# CA_kit_v02.net
KiCad netlist of a schematic drawn in EAGLE
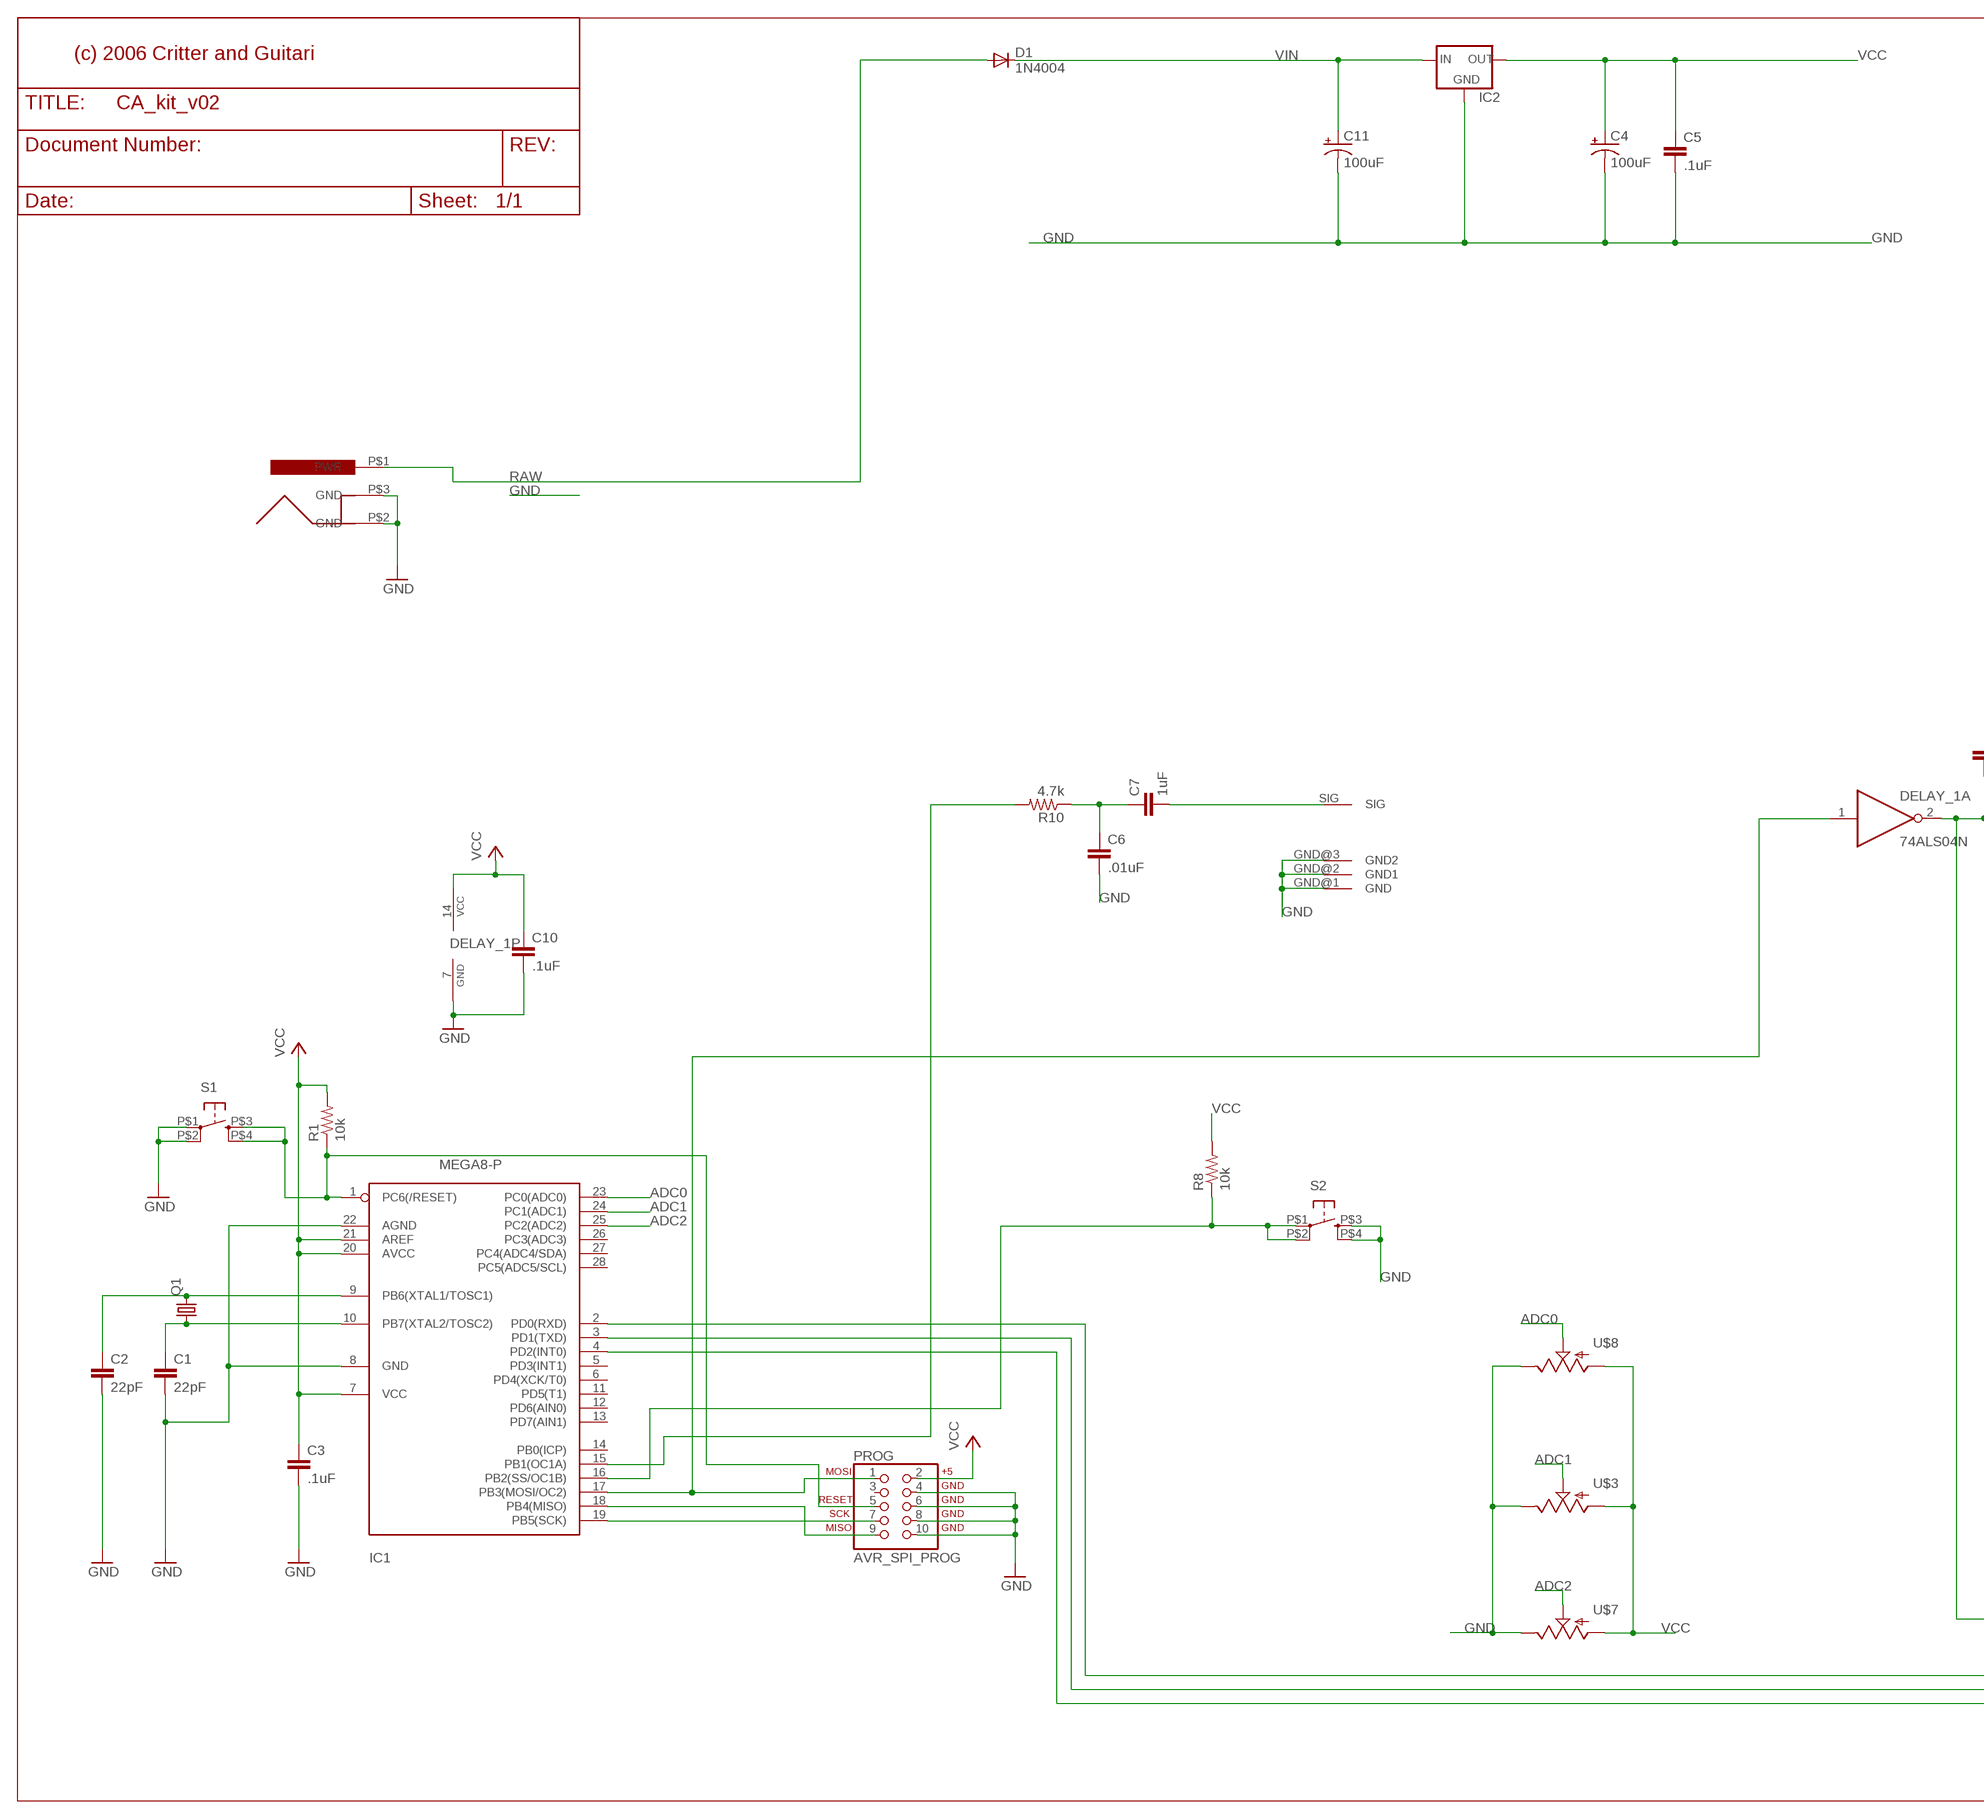
[diagram p0: schematic, sheet 1, part 1 of 2]
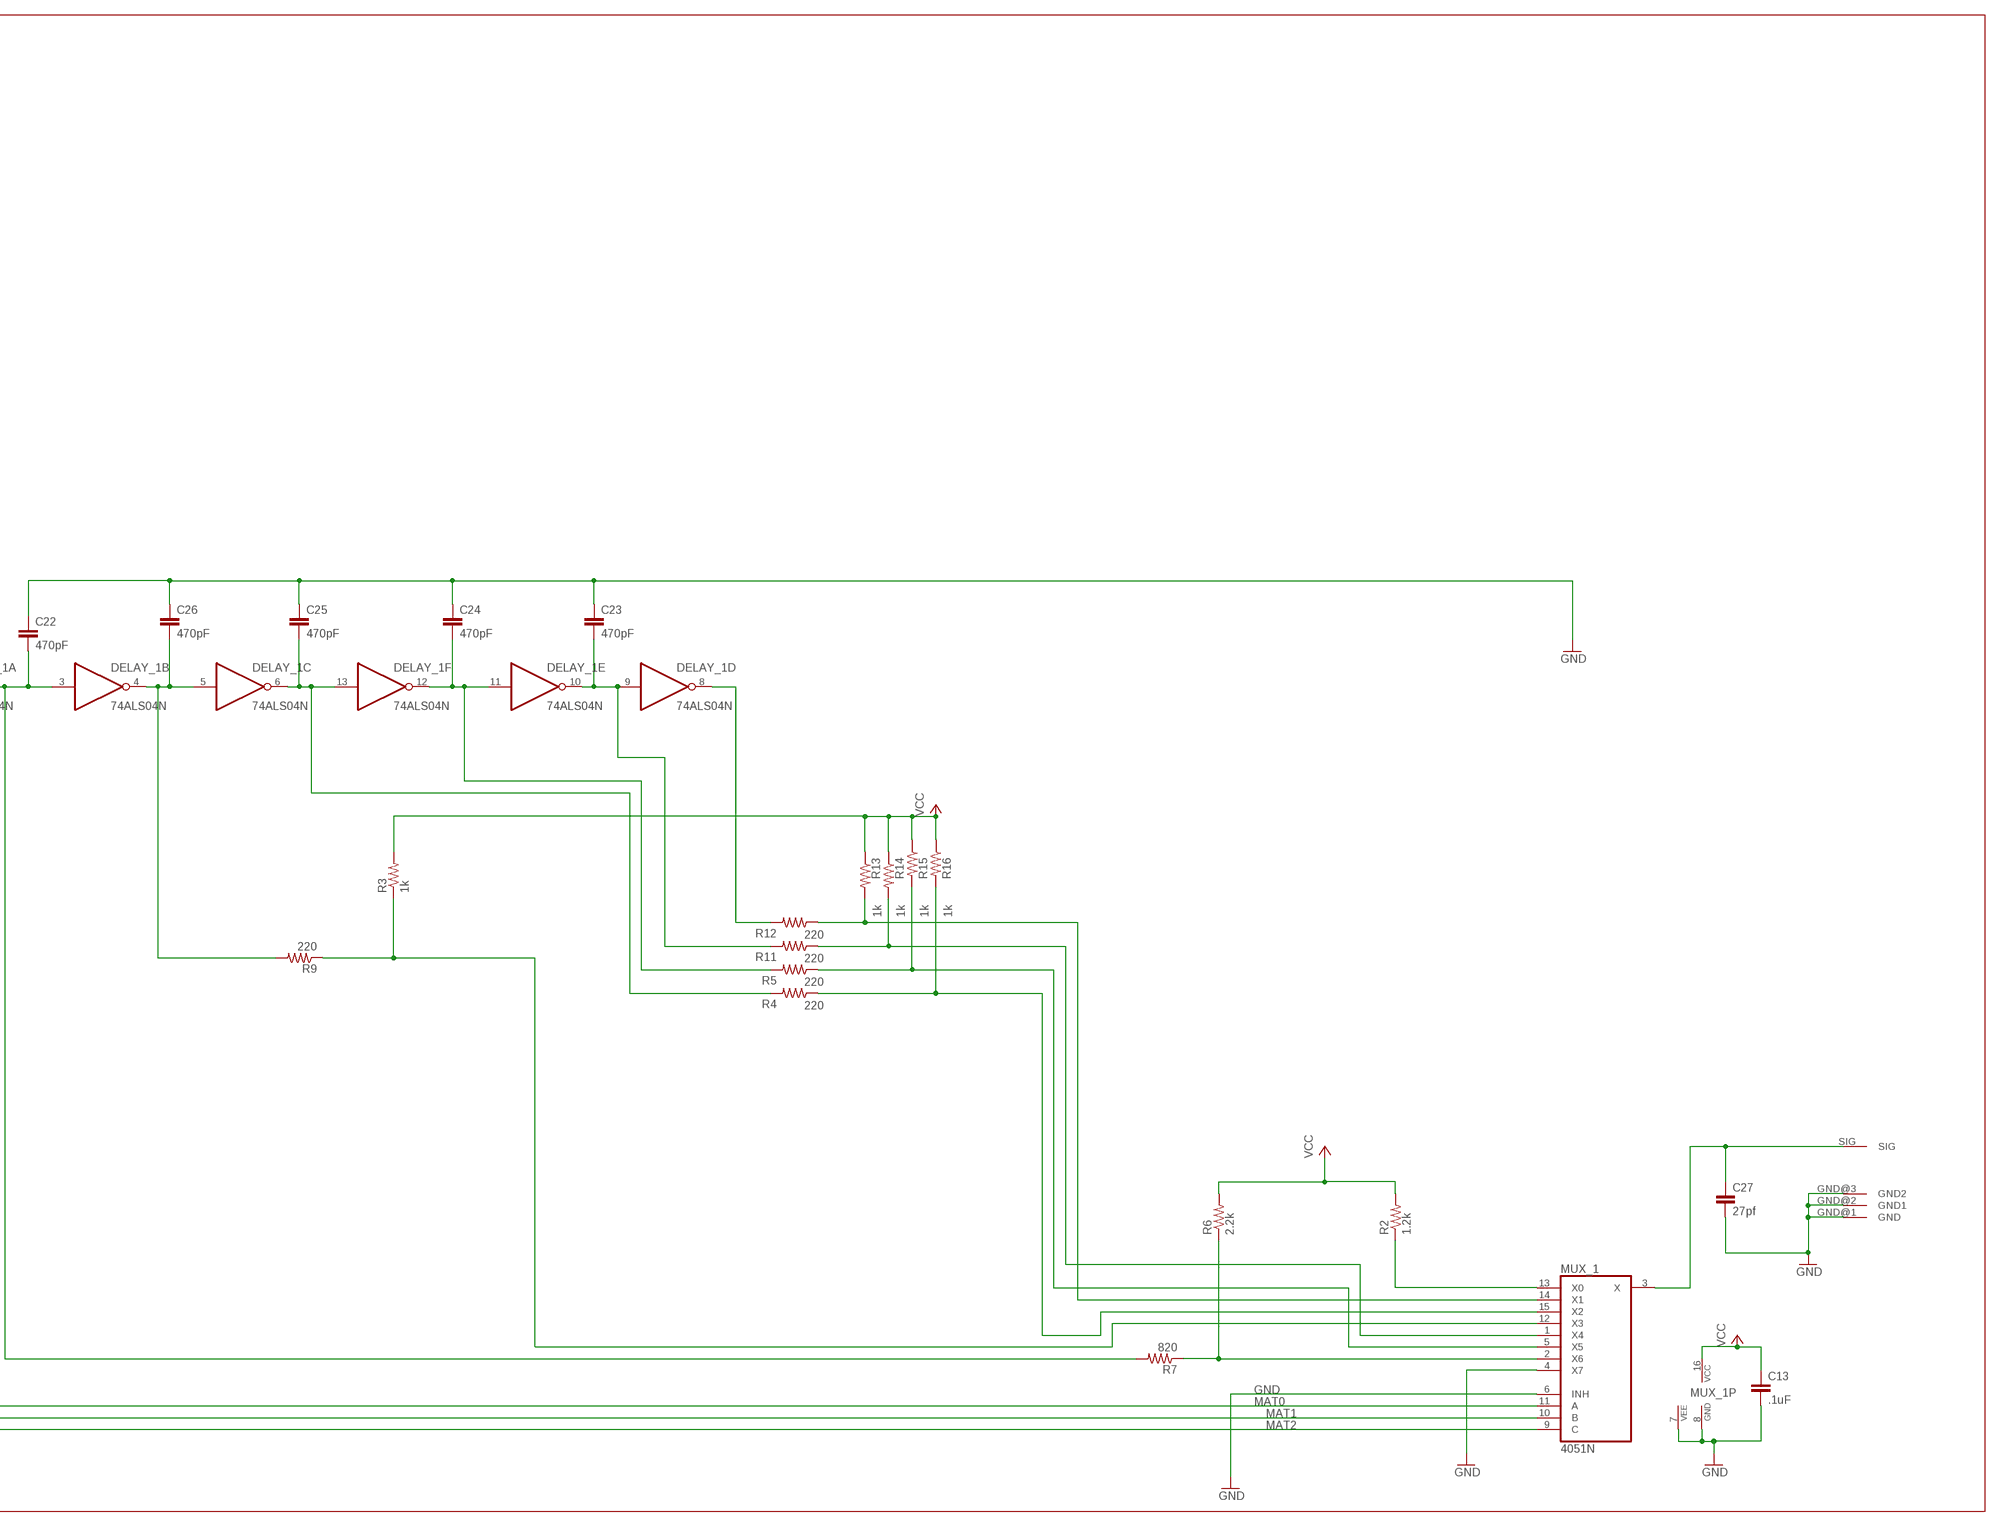
[diagram p1: schematic, sheet 1, part 2 of 2]

(export (version "E")
  (design (tool "Eeschema 10.0.6"))
  (components
    (comp (ref "C1")
      (value "22pF")
      (footprint "eagle-import:C025-025X050")
      (libsource (lib "eagle-import") (part "CAP025-025X050"))
    )
    (comp (ref "C2")
      (value "22pF")
      (footprint "eagle-import:C025-025X050")
      (libsource (lib "eagle-import") (part "CAP025-025X050"))
    )
    (comp (ref "C3")
      (value ".1uF")
      (footprint "eagle-import:C025-025X050")
      (libsource (lib "eagle-import") (part "CAP025-025X050"))
    )
    (comp (ref "C4")
      (value "100uF")
      (footprint "eagle-import:E3,5-8")
      (libsource (lib "eagle-import") (part "CPOL-USE3.5-8"))
    )
    (comp (ref "C5")
      (value ".1uF")
      (footprint "eagle-import:C025-025X050")
      (libsource (lib "eagle-import") (part "CAP025-025X050"))
    )
    (comp (ref "C6")
      (value ".01uF")
      (footprint "eagle-import:C025-025X050")
      (libsource (lib "eagle-import") (part "CAP025-025X050"))
    )
    (comp (ref "C7")
      (value "1uF")
      (footprint "eagle-import:C025-025X050")
      (libsource (lib "eagle-import") (part "CAP025-025X050"))
    )
    (comp (ref "C10")
      (value ".1uF")
      (footprint "eagle-import:C025-025X050")
      (libsource (lib "eagle-import") (part "CAP025-025X050"))
    )
    (comp (ref "C11")
      (value "100uF")
      (footprint "eagle-import:E3,5-8")
      (libsource (lib "eagle-import") (part "CPOL-USE3.5-8"))
    )
    (comp (ref "C13")
      (value ".1uF")
      (footprint "eagle-import:C025-025X050")
      (libsource (lib "eagle-import") (part "CAP025-025X050"))
    )
    (comp (ref "C22")
      (value "470pF")
      (footprint "eagle-import:C025-025X050")
      (libsource (lib "eagle-import") (part "CAP025-025X050"))
    )
    (comp (ref "C23")
      (value "470pF")
      (footprint "eagle-import:C025-025X050")
      (libsource (lib "eagle-import") (part "CAP025-025X050"))
    )
    (comp (ref "C24")
      (value "470pF")
      (footprint "eagle-import:C025-025X050")
      (libsource (lib "eagle-import") (part "CAP025-025X050"))
    )
    (comp (ref "C25")
      (value "470pF")
      (footprint "eagle-import:C025-025X050")
      (libsource (lib "eagle-import") (part "CAP025-025X050"))
    )
    (comp (ref "C26")
      (value "470pF")
      (footprint "eagle-import:C025-025X050")
      (libsource (lib "eagle-import") (part "CAP025-025X050"))
    )
    (comp (ref "C27")
      (value "27pf")
      (footprint "eagle-import:C025-025X050")
      (libsource (lib "eagle-import") (part "CAP025-025X050"))
    )
    (comp (ref "D1")
      (value "1N4004")
      (footprint "eagle-import:DO41-10")
      (libsource (lib "eagle-import") (part "1N4004"))
    )
    (comp (ref "DELAY_1")
      (value "74ALS04N")
      (footprint "eagle-import:DIL14")
      (libsource (lib "eagle-import") (part "7404NALS"))
    )
    (comp (ref "IC1")
      (value "MEGA8-P")
      (footprint "eagle-import:DIL28-3")
      (libsource (lib "eagle-import") (part "MEGA8-P"))
    )
    (comp (ref "IC2")
      (value "78XXS")
      (footprint "eagle-import:78XXS")
      (libsource (lib "eagle-import") (part "78XXS"))
    )
    (comp (ref "MUX_1")
      (value "4051N")
      (footprint "eagle-import:DIL16")
      (libsource (lib "eagle-import") (part "4051N"))
    )
    (comp (ref "PROG")
      (value "AVR_SPI_PROG")
      (footprint "eagle-import:PINHEAD_2X05")
      (libsource (lib "eagle-import") (part "AVR_SPI_PROG"))
    )
    (comp (ref "Q1")
      (value "CRYSTALHC49UV")
      (footprint "eagle-import:HC49U-V")
      (libsource (lib "eagle-import") (part "CRYSTALHC49UV"))
    )
    (comp (ref "R1")
      (value "10k")
      (footprint "eagle-import:0204V")
      (libsource (lib "eagle-import") (part "RES0204V"))
    )
    (comp (ref "R2")
      (value "1.2k")
      (footprint "eagle-import:0204V")
      (libsource (lib "eagle-import") (part "RES0204V"))
    )
    (comp (ref "R3")
      (value "1k")
      (footprint "eagle-import:0204V")
      (libsource (lib "eagle-import") (part "RES0204V"))
    )
    (comp (ref "R4")
      (value "220")
      (footprint "eagle-import:0204V")
      (libsource (lib "eagle-import") (part "RES0204V"))
    )
    (comp (ref "R5")
      (value "220")
      (footprint "eagle-import:0204V")
      (libsource (lib "eagle-import") (part "RES0204V"))
    )
    (comp (ref "R6")
      (value "2.2k")
      (footprint "eagle-import:0204V")
      (libsource (lib "eagle-import") (part "RES0204V"))
    )
    (comp (ref "R7")
      (value "820")
      (footprint "eagle-import:0204V")
      (libsource (lib "eagle-import") (part "RES0204V"))
    )
    (comp (ref "R8")
      (value "10k")
      (footprint "eagle-import:0204V")
      (libsource (lib "eagle-import") (part "RES0204V"))
    )
    (comp (ref "R9")
      (value "220")
      (footprint "eagle-import:0204V")
      (libsource (lib "eagle-import") (part "RES0204V"))
    )
    (comp (ref "R10")
      (value "4.7k")
      (footprint "eagle-import:0204V")
      (libsource (lib "eagle-import") (part "RES0204V"))
    )
    (comp (ref "R11")
      (value "220")
      (footprint "eagle-import:0204V")
      (libsource (lib "eagle-import") (part "RES0204V"))
    )
    (comp (ref "R12")
      (value "220")
      (footprint "eagle-import:0204V")
      (libsource (lib "eagle-import") (part "RES0204V"))
    )
    (comp (ref "R13")
      (value "1k")
      (footprint "eagle-import:0204V")
      (libsource (lib "eagle-import") (part "RES0204V"))
    )
    (comp (ref "R14")
      (value "1k")
      (footprint "eagle-import:0204V")
      (libsource (lib "eagle-import") (part "RES0204V"))
    )
    (comp (ref "R15")
      (value "1k")
      (footprint "eagle-import:0204V")
      (libsource (lib "eagle-import") (part "RES0204V"))
    )
    (comp (ref "R16")
      (value "1k")
      (footprint "eagle-import:0204V")
      (libsource (lib "eagle-import") (part "RES0204V"))
    )
    (comp (ref "S1")
      (value "TAC_SWITCHKSA_SEALED_TAC_SWITCH")
      (footprint "eagle-import:KSA_SEALED_TAC_SWITCH")
      (libsource (lib "eagle-import") (part "TAC_SWITCHKSA_SEALED_TAC_SWITCH"))
    )
    (comp (ref "S2")
      (value "TAC_SWITCHKSA_SEALED_TAC_SWITCH")
      (footprint "eagle-import:KSA_SEALED_TAC_SWITCH")
      (libsource (lib "eagle-import") (part "TAC_SWITCHKSA_SEALED_TAC_SWITCH"))
    )
    (comp (ref "U$1")
      (value "POWER_JACK")
      (footprint "eagle-import:POWER_JACK")
      (libsource (lib "eagle-import") (part "POWER_JACKTHRU-HOLE"))
    )
    (comp (ref "U$3")
      (value "POT")
      (footprint "eagle-import:ALPS_POT")
      (libsource (lib "eagle-import") (part "POT"))
    )
    (comp (ref "U$5")
      (value "PHONO_PLUG")
      (footprint "eagle-import:PHONO_PCB")
      (libsource (lib "eagle-import") (part "PHONO_PLUG"))
    )
    (comp (ref "U$6")
      (value "PHONO_PLUG")
      (footprint "eagle-import:PHONO_PCB")
      (libsource (lib "eagle-import") (part "PHONO_PLUG"))
    )
    (comp (ref "U$7")
      (value "POT")
      (footprint "eagle-import:ALPS_POT")
      (libsource (lib "eagle-import") (part "POT"))
    )
    (comp (ref "U$8")
      (value "POT")
      (footprint "eagle-import:ALPS_POT")
      (libsource (lib "eagle-import") (part "POT"))
    )
  )
  (nets
    (net (code "1") (name "/ADC0") (class "Default")
      (node (ref "IC1") (pin "23") (pinfunction "PC0(ADC0)_23") (pintype "bidirectional"))
      (node (ref "U$8") (pin "P$2") (pinfunction "S_P$2") (pintype "passive"))
    )
    (net (code "2") (name "/ADC1") (class "Default")
      (node (ref "IC1") (pin "24") (pinfunction "PC1(ADC1)_24") (pintype "bidirectional"))
      (node (ref "U$3") (pin "P$2") (pinfunction "S_P$2") (pintype "passive"))
    )
    (net (code "3") (name "/ADC2") (class "Default")
      (node (ref "IC1") (pin "25") (pinfunction "PC2(ADC2)_25") (pintype "bidirectional"))
      (node (ref "U$7") (pin "P$2") (pinfunction "S_P$2") (pintype "passive"))
    )
    (net (code "4") (name "/MAT0") (class "Default")
      (node (ref "IC1") (pin "2") (pinfunction "PD0(RXD)_2") (pintype "bidirectional"))
      (node (ref "MUX_1") (pin "11") (pinfunction "A_11") (pintype "input"))
    )
    (net (code "5") (name "/MAT1") (class "Default")
      (node (ref "IC1") (pin "3") (pinfunction "PD1(TXD)_3") (pintype "bidirectional"))
      (node (ref "MUX_1") (pin "10") (pinfunction "B_10") (pintype "input"))
    )
    (net (code "6") (name "/MAT2") (class "Default")
      (node (ref "IC1") (pin "4") (pinfunction "PD2(INT0)_4") (pintype "bidirectional"))
      (node (ref "MUX_1") (pin "9") (pinfunction "C_9") (pintype "input"))
    )
    (net (code "7") (name "/RAW") (class "Default")
      (node (ref "D1") (pin "A") (pinfunction "A_A") (pintype "passive"))
      (node (ref "U$1") (pin "P$1") (pinfunction "PWR_P$1") (pintype "bidirectional"))
    )
    (net (code "8") (name "/VIN") (class "Default")
      (node (ref "C11") (pin "+") (pinfunction "+_+") (pintype "passive"))
      (node (ref "D1") (pin "C") (pinfunction "C_C") (pintype "passive"))
      (node (ref "IC2") (pin "IN") (pinfunction "IN_IN") (pintype "input"))
    )
    (net (code "9") (name "GND") (class "Default")
      (node (ref "C1") (pin "2") (pinfunction "2_2") (pintype "passive"))
      (node (ref "C10") (pin "2") (pinfunction "2_2") (pintype "passive"))
      (node (ref "C11") (pin "-") (pinfunction "-_-") (pintype "passive"))
      (node (ref "C13") (pin "2") (pinfunction "2_2") (pintype "passive"))
      (node (ref "C2") (pin "2") (pinfunction "2_2") (pintype "passive"))
      (node (ref "C22") (pin "1") (pinfunction "1_1") (pintype "passive"))
      (node (ref "C23") (pin "1") (pinfunction "1_1") (pintype "passive"))
      (node (ref "C24") (pin "1") (pinfunction "1_1") (pintype "passive"))
      (node (ref "C25") (pin "1") (pinfunction "1_1") (pintype "passive"))
      (node (ref "C26") (pin "1") (pinfunction "1_1") (pintype "passive"))
      (node (ref "C27") (pin "2") (pinfunction "2_2") (pintype "passive"))
      (node (ref "C3") (pin "2") (pinfunction "2_2") (pintype "passive"))
      (node (ref "C4") (pin "-") (pinfunction "-_-") (pintype "passive"))
      (node (ref "C5") (pin "2") (pinfunction "2_2") (pintype "passive"))
      (node (ref "C6") (pin "2") (pinfunction "2_2") (pintype "passive"))
      (node (ref "DELAY_1") (pin "7") (pinfunction "GND_7") (pintype "power_in"))
      (node (ref "IC1") (pin "22") (pinfunction "AGND_22") (pintype "bidirectional"))
      (node (ref "IC1") (pin "8") (pinfunction "GND_8") (pintype "bidirectional"))
      (node (ref "IC2") (pin "GND") (pinfunction "GND_GND") (pintype "input"))
      (node (ref "MUX_1") (pin "4") (pinfunction "X7_4") (pintype "bidirectional"))
      (node (ref "MUX_1") (pin "6") (pinfunction "INH_6") (pintype "input"))
      (node (ref "MUX_1") (pin "7") (pinfunction "VEE_7") (pintype "power_in"))
      (node (ref "MUX_1") (pin "8") (pinfunction "GND_8") (pintype "power_in"))
      (node (ref "PROG") (pin "10") (pinfunction "10_10") (pintype "passive"))
      (node (ref "PROG") (pin "4") (pinfunction "4_4") (pintype "passive"))
      (node (ref "PROG") (pin "6") (pinfunction "6_6") (pintype "passive"))
      (node (ref "PROG") (pin "8") (pinfunction "8_8") (pintype "passive"))
      (node (ref "S1") (pin "P$1") (pinfunction "P_P$1") (pintype "passive"))
      (node (ref "S1") (pin "P$2") (pinfunction "P1_P$2") (pintype "passive"))
      (node (ref "S2") (pin "P$3") (pinfunction "S_P$3") (pintype "passive"))
      (node (ref "S2") (pin "P$4") (pinfunction "S1_P$4") (pintype "passive"))
      (node (ref "U$1") (pin "P$2") (pinfunction "GND_P$2") (pintype "bidirectional"))
      (node (ref "U$1") (pin "P$3") (pinfunction "GND_P$3") (pintype "bidirectional"))
      (node (ref "U$3") (pin "P$1") (pinfunction "E_P$1") (pintype "passive"))
      (node (ref "U$5") (pin "GND@1") (pinfunction "GND_GND@1") (pintype "bidirectional"))
      (node (ref "U$5") (pin "GND@2") (pinfunction "GND1_GND@2") (pintype "bidirectional"))
      (node (ref "U$5") (pin "GND@3") (pinfunction "GND2_GND@3") (pintype "bidirectional"))
      (node (ref "U$6") (pin "GND@1") (pinfunction "GND_GND@1") (pintype "bidirectional"))
      (node (ref "U$6") (pin "GND@2") (pinfunction "GND1_GND@2") (pintype "bidirectional"))
      (node (ref "U$6") (pin "GND@3") (pinfunction "GND2_GND@3") (pintype "bidirectional"))
      (node (ref "U$7") (pin "P$1") (pinfunction "E_P$1") (pintype "passive"))
      (node (ref "U$8") (pin "P$1") (pinfunction "E_P$1") (pintype "passive"))
    )
    (net (code "10") (name "Net-(C6-Pad1)") (class "Default")
      (node (ref "C6") (pin "1") (pinfunction "1_1") (pintype "passive"))
      (node (ref "C7") (pin "1") (pinfunction "1_1") (pintype "passive"))
      (node (ref "R10") (pin "1") (pinfunction "1_1") (pintype "passive"))
    )
    (net (code "11") (name "Net-(C7-Pad2)") (class "Default")
      (node (ref "C7") (pin "2") (pinfunction "2_2") (pintype "passive"))
      (node (ref "U$5") (pin "SIG") (pinfunction "SIG_SIG") (pintype "bidirectional"))
    )
    (net (code "12") (name "Net-(DELAY_1A-I)") (class "Default")
      (node (ref "DELAY_1") (pin "1") (pinfunction "I_1") (pintype "input"))
      (node (ref "IC1") (pin "17") (pinfunction "PB3(MOSI/OC2)_17") (pintype "bidirectional"))
      (node (ref "PROG") (pin "1") (pinfunction "1_1") (pintype "passive"))
    )
    (net (code "13") (name "Net-(DELAY_1A-O)") (class "Default")
      (node (ref "C22") (pin "2") (pinfunction "2_2") (pintype "passive"))
      (node (ref "DELAY_1") (pin "2") (pinfunction "O_2") (pintype "output"))
      (node (ref "DELAY_1") (pin "3") (pinfunction "I_3") (pintype "input"))
      (node (ref "R7") (pin "2") (pinfunction "2_2") (pintype "passive"))
    )
    (net (code "14") (name "Net-(DELAY_1B-O)") (class "Default")
      (node (ref "C26") (pin "2") (pinfunction "2_2") (pintype "passive"))
      (node (ref "DELAY_1") (pin "4") (pinfunction "O_4") (pintype "output"))
      (node (ref "DELAY_1") (pin "5") (pinfunction "I_5") (pintype "input"))
      (node (ref "R9") (pin "2") (pinfunction "2_2") (pintype "passive"))
    )
    (net (code "15") (name "Net-(DELAY_1C-O)") (class "Default")
      (node (ref "C25") (pin "2") (pinfunction "2_2") (pintype "passive"))
      (node (ref "DELAY_1") (pin "13") (pinfunction "I_13") (pintype "input"))
      (node (ref "DELAY_1") (pin "6") (pinfunction "O_6") (pintype "output"))
      (node (ref "R4") (pin "2") (pinfunction "2_2") (pintype "passive"))
    )
    (net (code "16") (name "Net-(DELAY_1D-I)") (class "Default")
      (node (ref "C23") (pin "2") (pinfunction "2_2") (pintype "passive"))
      (node (ref "DELAY_1") (pin "10") (pinfunction "O_10") (pintype "output"))
      (node (ref "DELAY_1") (pin "9") (pinfunction "I_9") (pintype "input"))
      (node (ref "R11") (pin "2") (pinfunction "2_2") (pintype "passive"))
    )
    (net (code "17") (name "Net-(DELAY_1D-O)") (class "Default")
      (node (ref "DELAY_1") (pin "8") (pinfunction "O_8") (pintype "output"))
      (node (ref "R12") (pin "2") (pinfunction "2_2") (pintype "passive"))
    )
    (net (code "18") (name "Net-(DELAY_1E-I)") (class "Default")
      (node (ref "C24") (pin "2") (pinfunction "2_2") (pintype "passive"))
      (node (ref "DELAY_1") (pin "11") (pinfunction "I_11") (pintype "input"))
      (node (ref "DELAY_1") (pin "12") (pinfunction "O_12") (pintype "output"))
      (node (ref "R5") (pin "2") (pinfunction "2_2") (pintype "passive"))
    )
    (net (code "19") (name "Net-(IC1-PB1(OC1A))") (class "Default")
      (node (ref "IC1") (pin "15") (pinfunction "PB1(OC1A)_15") (pintype "bidirectional"))
      (node (ref "R10") (pin "2") (pinfunction "2_2") (pintype "passive"))
    )
    (net (code "20") (name "Net-(IC1-PB2(SS{slash}OC1B))") (class "Default")
      (node (ref "IC1") (pin "16") (pinfunction "PB2(SS/OC1B)_16") (pintype "bidirectional"))
      (node (ref "R8") (pin "1") (pinfunction "1_1") (pintype "passive"))
      (node (ref "S2") (pin "P$1") (pinfunction "P_P$1") (pintype "passive"))
      (node (ref "S2") (pin "P$2") (pinfunction "P1_P$2") (pintype "passive"))
    )
    (net (code "21") (name "Net-(IC1-PB4(MISO))") (class "Default")
      (node (ref "IC1") (pin "18") (pinfunction "PB4(MISO)_18") (pintype "bidirectional"))
      (node (ref "PROG") (pin "9") (pinfunction "9_9") (pintype "passive"))
    )
    (net (code "22") (name "Net-(IC1-PB5(SCK))") (class "Default")
      (node (ref "IC1") (pin "19") (pinfunction "PB5(SCK)_19") (pintype "bidirectional"))
      (node (ref "PROG") (pin "7") (pinfunction "7_7") (pintype "passive"))
    )
    (net (code "23") (name "Net-(IC1-PB6(XTAL1{slash}TOSC1))") (class "Default")
      (node (ref "C2") (pin "1") (pinfunction "1_1") (pintype "passive"))
      (node (ref "IC1") (pin "9") (pinfunction "PB6(XTAL1/TOSC1)_9") (pintype "bidirectional"))
      (node (ref "Q1") (pin "2") (pinfunction "2_2") (pintype "passive"))
    )
    (net (code "24") (name "Net-(IC1-PB7(XTAL2{slash}TOSC2))") (class "Default")
      (node (ref "C1") (pin "1") (pinfunction "1_1") (pintype "passive"))
      (node (ref "IC1") (pin "10") (pinfunction "PB7(XTAL2/TOSC2)_10") (pintype "bidirectional"))
      (node (ref "Q1") (pin "1") (pinfunction "1_1") (pintype "passive"))
    )
    (net (code "25") (name "Net-(IC1-PC6({slash}RESET))") (class "Default")
      (node (ref "IC1") (pin "1") (pinfunction "PC6(/RESET)_1") (pintype "bidirectional"))
      (node (ref "PROG") (pin "5") (pinfunction "5_5") (pintype "passive"))
      (node (ref "R1") (pin "1") (pinfunction "1_1") (pintype "passive"))
      (node (ref "S1") (pin "P$3") (pinfunction "S_P$3") (pintype "passive"))
      (node (ref "S1") (pin "P$4") (pinfunction "S1_P$4") (pintype "passive"))
    )
    (net (code "26") (name "Net-(MUX_1A-X)") (class "Default")
      (node (ref "C27") (pin "1") (pinfunction "1_1") (pintype "passive"))
      (node (ref "MUX_1") (pin "3") (pinfunction "X_3") (pintype "bidirectional"))
      (node (ref "U$6") (pin "SIG") (pinfunction "SIG_SIG") (pintype "bidirectional"))
    )
    (net (code "27") (name "Net-(MUX_1A-X0)") (class "Default")
      (node (ref "MUX_1") (pin "13") (pinfunction "X0_13") (pintype "bidirectional"))
      (node (ref "R2") (pin "1") (pinfunction "1_1") (pintype "passive"))
    )
    (net (code "28") (name "Net-(MUX_1A-X1)") (class "Default")
      (node (ref "MUX_1") (pin "14") (pinfunction "X1_14") (pintype "bidirectional"))
      (node (ref "R12") (pin "1") (pinfunction "1_1") (pintype "passive"))
      (node (ref "R13") (pin "2") (pinfunction "2_2") (pintype "passive"))
    )
    (net (code "29") (name "Net-(MUX_1A-X2)") (class "Default")
      (node (ref "MUX_1") (pin "15") (pinfunction "X2_15") (pintype "bidirectional"))
      (node (ref "R16") (pin "2") (pinfunction "2_2") (pintype "passive"))
      (node (ref "R4") (pin "1") (pinfunction "1_1") (pintype "passive"))
    )
    (net (code "30") (name "Net-(MUX_1A-X3)") (class "Default")
      (node (ref "MUX_1") (pin "12") (pinfunction "X3_12") (pintype "bidirectional"))
      (node (ref "R3") (pin "1") (pinfunction "1_1") (pintype "passive"))
      (node (ref "R9") (pin "1") (pinfunction "1_1") (pintype "passive"))
    )
    (net (code "31") (name "Net-(MUX_1A-X4)") (class "Default")
      (node (ref "MUX_1") (pin "1") (pinfunction "X4_1") (pintype "bidirectional"))
      (node (ref "R11") (pin "1") (pinfunction "1_1") (pintype "passive"))
      (node (ref "R14") (pin "2") (pinfunction "2_2") (pintype "passive"))
    )
    (net (code "32") (name "Net-(MUX_1A-X5)") (class "Default")
      (node (ref "MUX_1") (pin "5") (pinfunction "X5_5") (pintype "bidirectional"))
      (node (ref "R15") (pin "2") (pinfunction "2_2") (pintype "passive"))
      (node (ref "R5") (pin "1") (pinfunction "1_1") (pintype "passive"))
    )
    (net (code "33") (name "Net-(MUX_1A-X6)") (class "Default")
      (node (ref "MUX_1") (pin "2") (pinfunction "X6_2") (pintype "bidirectional"))
      (node (ref "R6") (pin "1") (pinfunction "1_1") (pintype "passive"))
      (node (ref "R7") (pin "1") (pinfunction "1_1") (pintype "passive"))
    )
    (net (code "34") (name "VCC") (class "Default")
      (node (ref "C10") (pin "1") (pinfunction "1_1") (pintype "passive"))
      (node (ref "C13") (pin "1") (pinfunction "1_1") (pintype "passive"))
      (node (ref "C3") (pin "1") (pinfunction "1_1") (pintype "passive"))
      (node (ref "C4") (pin "+") (pinfunction "+_+") (pintype "passive"))
      (node (ref "C5") (pin "1") (pinfunction "1_1") (pintype "passive"))
      (node (ref "DELAY_1") (pin "14") (pinfunction "VCC_14") (pintype "power_in"))
      (node (ref "IC1") (pin "20") (pinfunction "AVCC_20") (pintype "bidirectional"))
      (node (ref "IC1") (pin "21") (pinfunction "AREF_21") (pintype "bidirectional"))
      (node (ref "IC1") (pin "7") (pinfunction "VCC_7") (pintype "bidirectional"))
      (node (ref "IC2") (pin "OUT") (pinfunction "OUT_OUT") (pintype "passive"))
      (node (ref "MUX_1") (pin "16") (pinfunction "VCC_16") (pintype "power_in"))
      (node (ref "PROG") (pin "2") (pinfunction "2_2") (pintype "passive"))
      (node (ref "R1") (pin "2") (pinfunction "2_2") (pintype "passive"))
      (node (ref "R13") (pin "1") (pinfunction "1_1") (pintype "passive"))
      (node (ref "R14") (pin "1") (pinfunction "1_1") (pintype "passive"))
      (node (ref "R15") (pin "1") (pinfunction "1_1") (pintype "passive"))
      (node (ref "R16") (pin "1") (pinfunction "1_1") (pintype "passive"))
      (node (ref "R2") (pin "2") (pinfunction "2_2") (pintype "passive"))
      (node (ref "R3") (pin "2") (pinfunction "2_2") (pintype "passive"))
      (node (ref "R6") (pin "2") (pinfunction "2_2") (pintype "passive"))
      (node (ref "R8") (pin "2") (pinfunction "2_2") (pintype "passive"))
      (node (ref "U$3") (pin "P$3") (pinfunction "A_P$3") (pintype "passive"))
      (node (ref "U$7") (pin "P$3") (pinfunction "A_P$3") (pintype "passive"))
      (node (ref "U$8") (pin "P$3") (pinfunction "A_P$3") (pintype "passive"))
    )
    (net (code "35") (name "unconnected-(IC1-PB0(ICP)-Pad14)") (class "Default")
      (node (ref "IC1") (pin "14") (pinfunction "PB0(ICP)_14") (pintype "bidirectional"))
    )
    (net (code "36") (name "unconnected-(IC1-PC3(ADC3)-Pad26)") (class "Default")
      (node (ref "IC1") (pin "26") (pinfunction "PC3(ADC3)_26") (pintype "bidirectional"))
    )
    (net (code "37") (name "unconnected-(IC1-PC4(ADC4{slash}SDA)-Pad27)") (class "Default")
      (node (ref "IC1") (pin "27") (pinfunction "PC4(ADC4/SDA)_27") (pintype "bidirectional"))
    )
    (net (code "38") (name "unconnected-(IC1-PC5(ADC5{slash}SCL)-Pad28)") (class "Default")
      (node (ref "IC1") (pin "28") (pinfunction "PC5(ADC5/SCL)_28") (pintype "bidirectional"))
    )
    (net (code "39") (name "unconnected-(IC1-PD3(INT1)-Pad5)") (class "Default")
      (node (ref "IC1") (pin "5") (pinfunction "PD3(INT1)_5") (pintype "bidirectional"))
    )
    (net (code "40") (name "unconnected-(IC1-PD4(XCK{slash}T0)-Pad6)") (class "Default")
      (node (ref "IC1") (pin "6") (pinfunction "PD4(XCK/T0)_6") (pintype "bidirectional"))
    )
    (net (code "41") (name "unconnected-(IC1-PD5(T1)-Pad11)") (class "Default")
      (node (ref "IC1") (pin "11") (pinfunction "PD5(T1)_11") (pintype "bidirectional"))
    )
    (net (code "42") (name "unconnected-(IC1-PD6(AIN0)-Pad12)") (class "Default")
      (node (ref "IC1") (pin "12") (pinfunction "PD6(AIN0)_12") (pintype "bidirectional"))
    )
    (net (code "43") (name "unconnected-(IC1-PD7(AIN1)-Pad13)") (class "Default")
      (node (ref "IC1") (pin "13") (pinfunction "PD7(AIN1)_13") (pintype "bidirectional"))
    )
    (net (code "44") (name "unconnected-(PROG-Pad3)") (class "Default")
      (node (ref "PROG") (pin "3") (pinfunction "3_3") (pintype "passive"))
    )
  )
)
